# cat.net
KiCad netlist of a schematic drawn in EAGLE
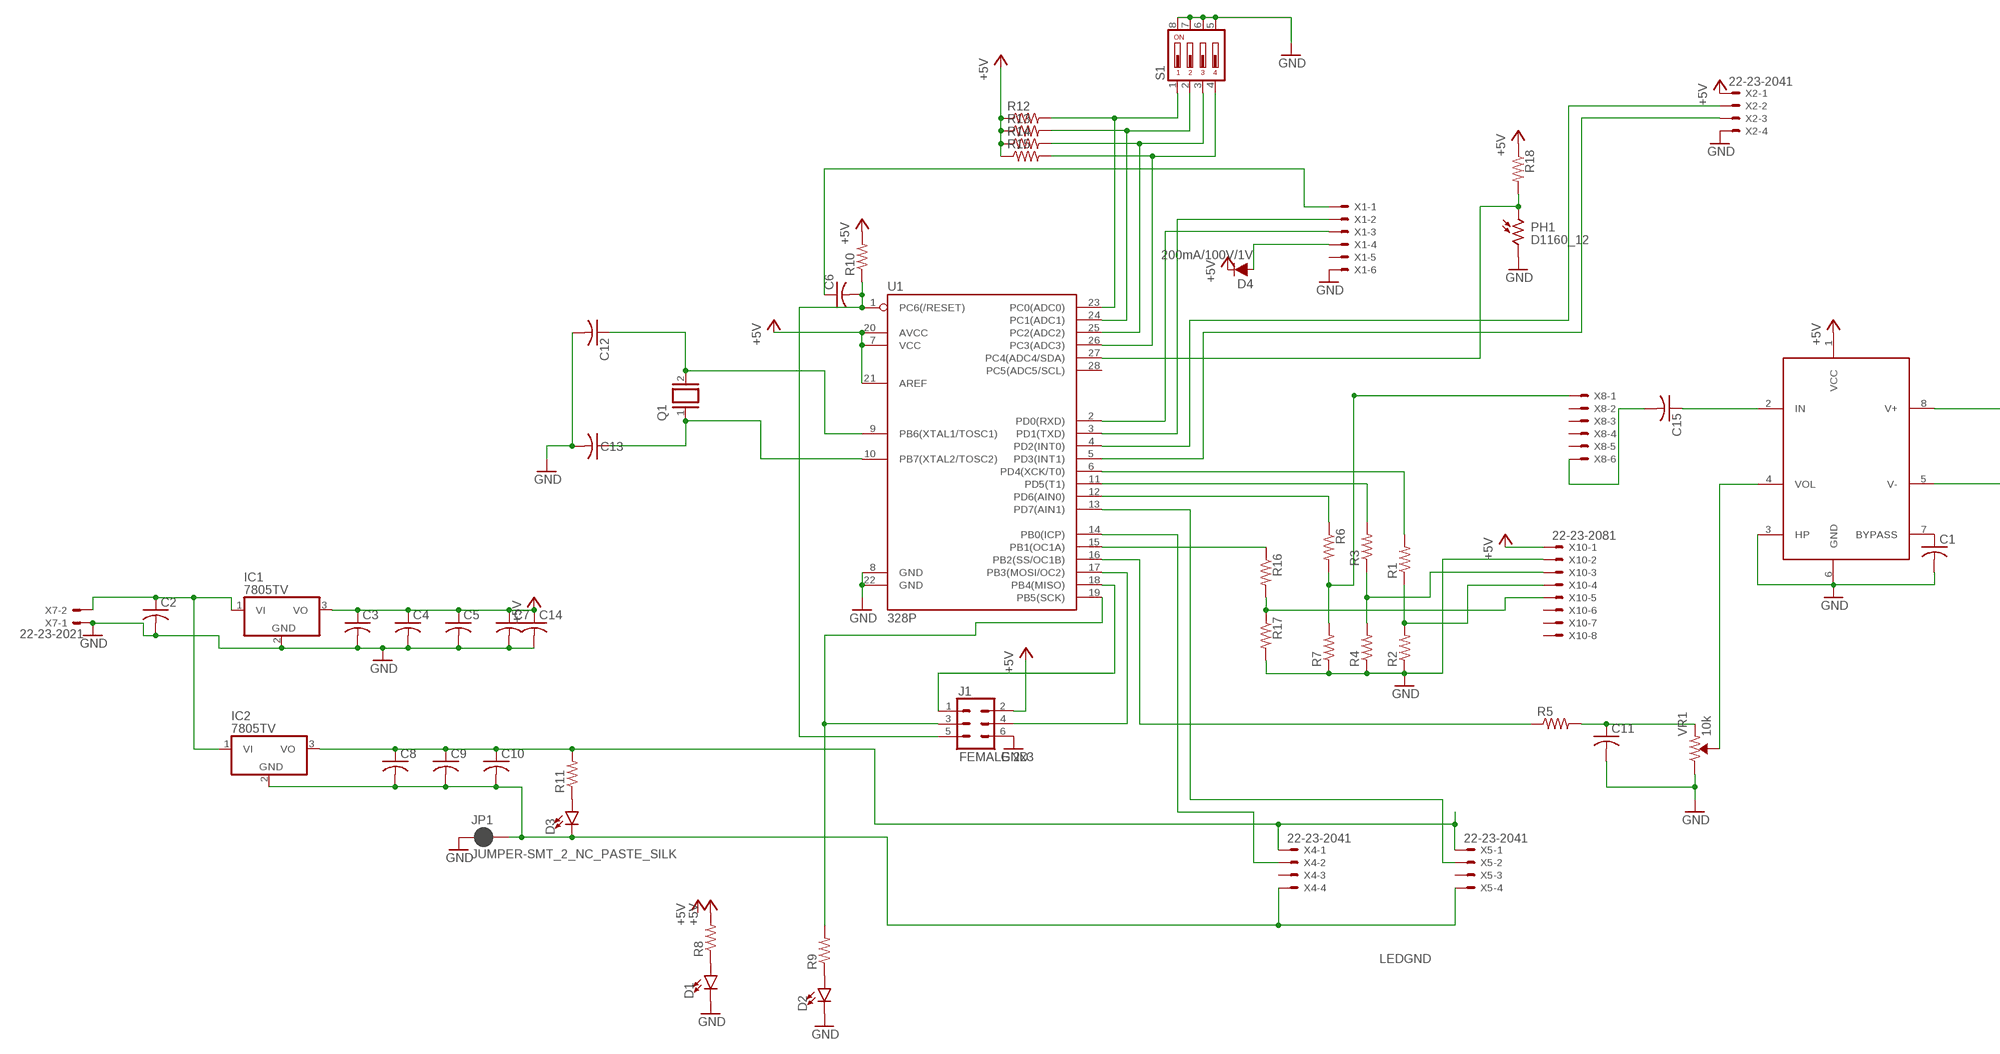
[diagram p0: schematic, sheet 1, part 1 of 2]
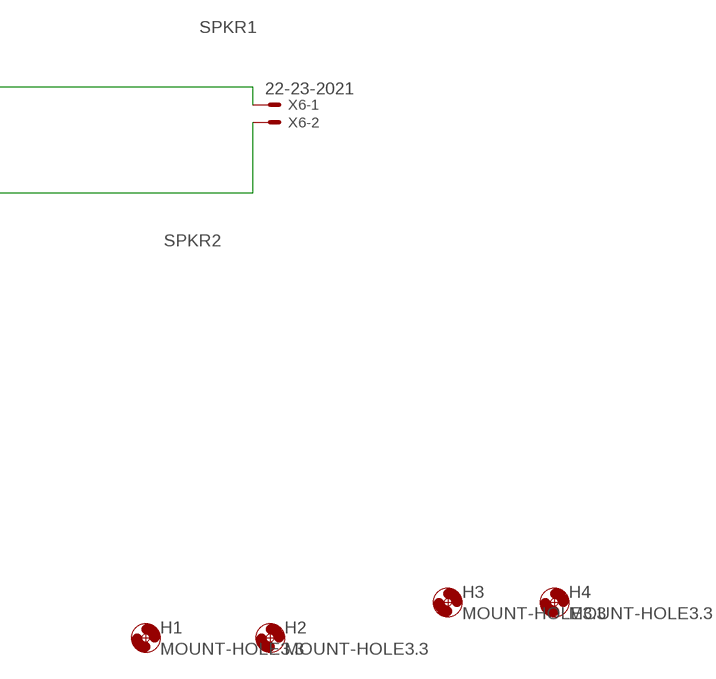
[diagram p1: schematic, sheet 1, part 2 of 2]

(export (version "E")
  (design (tool "Eeschema 10.0.6"))
  (components
    (comp (ref "C1")
      (value "C-US025-024X044")
      (footprint "eagle-import:C025-024X044")
      (libsource (lib "eagle-import") (part "C-US025-024X044"))
    )
    (comp (ref "C2")
      (value "C-US025-024X044")
      (footprint "eagle-import:C025-024X044")
      (libsource (lib "eagle-import") (part "C-US025-024X044"))
    )
    (comp (ref "C3")
      (value "C-US025-024X044")
      (footprint "eagle-import:C025-024X044")
      (libsource (lib "eagle-import") (part "C-US025-024X044"))
    )
    (comp (ref "C4")
      (value "C-US025-024X044")
      (footprint "eagle-import:C025-024X044")
      (libsource (lib "eagle-import") (part "C-US025-024X044"))
    )
    (comp (ref "C5")
      (value "C-US025-024X044")
      (footprint "eagle-import:C025-024X044")
      (libsource (lib "eagle-import") (part "C-US025-024X044"))
    )
    (comp (ref "C6")
      (value "C-US025-024X044")
      (footprint "eagle-import:C025-024X044")
      (libsource (lib "eagle-import") (part "C-US025-024X044"))
    )
    (comp (ref "C7")
      (value "C-US025-024X044")
      (footprint "eagle-import:C025-024X044")
      (libsource (lib "eagle-import") (part "C-US025-024X044"))
    )
    (comp (ref "C8")
      (value "C-US025-024X044")
      (footprint "eagle-import:C025-024X044")
      (libsource (lib "eagle-import") (part "C-US025-024X044"))
    )
    (comp (ref "C9")
      (value "C-US025-024X044")
      (footprint "eagle-import:C025-024X044")
      (libsource (lib "eagle-import") (part "C-US025-024X044"))
    )
    (comp (ref "C10")
      (value "C-US025-024X044")
      (footprint "eagle-import:C025-024X044")
      (libsource (lib "eagle-import") (part "C-US025-024X044"))
    )
    (comp (ref "C11")
      (value "C-US025-024X044")
      (footprint "eagle-import:C025-024X044")
      (libsource (lib "eagle-import") (part "C-US025-024X044"))
    )
    (comp (ref "C12")
      (value "C-US025-024X044")
      (footprint "eagle-import:C025-024X044")
      (libsource (lib "eagle-import") (part "C-US025-024X044"))
    )
    (comp (ref "C13")
      (value "C-US025-024X044")
      (footprint "eagle-import:C025-024X044")
      (libsource (lib "eagle-import") (part "C-US025-024X044"))
    )
    (comp (ref "C14")
      (value "C-US025-024X044")
      (footprint "eagle-import:C025-024X044")
      (libsource (lib "eagle-import") (part "C-US025-024X044"))
    )
    (comp (ref "C15")
      (value "C-US025-024X044")
      (footprint "eagle-import:C025-024X044")
      (libsource (lib "eagle-import") (part "C-US025-024X044"))
    )
    (comp (ref "D1")
      (value "LED-3MM-NO_SILK")
      (footprint "eagle-import:LED_3MM-NS")
      (libsource (lib "eagle-import") (part "LED-3MM-NO_SILK"))
    )
    (comp (ref "D2")
      (value "LED-3MM-NO_SILK")
      (footprint "eagle-import:LED_3MM-NS")
      (libsource (lib "eagle-import") (part "LED-3MM-NO_SILK"))
    )
    (comp (ref "D3")
      (value "LED-3MM-NO_SILK")
      (footprint "eagle-import:LED_3MM-NS")
      (libsource (lib "eagle-import") (part "LED-3MM-NO_SILK"))
    )
    (comp (ref "D4")
      (value "200mA/100V/1V")
      (footprint "eagle-import:DIODE-1N4148")
      (libsource (lib "eagle-import") (part "DIODE-1N4148"))
    )
    (comp (ref "H1")
      (value "MOUNT-HOLE3.3")
      (footprint "eagle-import:3,3")
      (libsource (lib "eagle-import") (part "MOUNT-HOLE3.3"))
    )
    (comp (ref "H2")
      (value "MOUNT-HOLE3.3")
      (footprint "eagle-import:3,3")
      (libsource (lib "eagle-import") (part "MOUNT-HOLE3.3"))
    )
    (comp (ref "H3")
      (value "MOUNT-HOLE3.3")
      (footprint "eagle-import:3,3")
      (libsource (lib "eagle-import") (part "MOUNT-HOLE3.3"))
    )
    (comp (ref "H4")
      (value "MOUNT-HOLE3.3")
      (footprint "eagle-import:3,3")
      (libsource (lib "eagle-import") (part "MOUNT-HOLE3.3"))
    )
    (comp (ref "IC1")
      (value "7805TV")
      (footprint "eagle-import:TO220V")
      (libsource (lib "eagle-import") (part "78TV05"))
    )
    (comp (ref "IC2")
      (value "7805TV")
      (footprint "eagle-import:TO220V")
      (libsource (lib "eagle-import") (part "78TV05"))
    )
    (comp (ref "J1")
      (value "FEMALE 2x3")
      (footprint "eagle-import:2X3")
      (libsource (lib "eagle-import") (part "CONN_03X2FEMALE"))
    )
    (comp (ref "JP1")
      (value "JUMPER-SMT_2_NC_PASTE_SILK")
      (footprint "eagle-import:SMT-JUMPER_2_NC_PASTE_SILK")
      (libsource (lib "eagle-import") (part "JUMPER-SMT_2_NC_PASTE_SILK"))
    )
    (comp (ref "PH1")
      (value "D1160_12")
      (footprint "eagle-import:D11XX")
      (libsource (lib "eagle-import") (part "D1160_12"))
    )
    (comp (ref "Q1")
      (value "XTAL/S")
      (footprint "eagle-import:QS")
      (libsource (lib "eagle-import") (part "XTAL/S"))
    )
    (comp (ref "R1")
      (value "R-US_R0805")
      (footprint "eagle-import:R0805")
      (libsource (lib "eagle-import") (part "R-US_R0805"))
    )
    (comp (ref "R2")
      (value "R-US_R0805")
      (footprint "eagle-import:R0805")
      (libsource (lib "eagle-import") (part "R-US_R0805"))
    )
    (comp (ref "R3")
      (value "R-US_R0805")
      (footprint "eagle-import:R0805")
      (libsource (lib "eagle-import") (part "R-US_R0805"))
    )
    (comp (ref "R4")
      (value "R-US_R0805")
      (footprint "eagle-import:R0805")
      (libsource (lib "eagle-import") (part "R-US_R0805"))
    )
    (comp (ref "R5")
      (value "R-US_R0805")
      (footprint "eagle-import:R0805")
      (libsource (lib "eagle-import") (part "R-US_R0805"))
    )
    (comp (ref "R6")
      (value "R-US_R0805")
      (footprint "eagle-import:R0805")
      (libsource (lib "eagle-import") (part "R-US_R0805"))
    )
    (comp (ref "R7")
      (value "R-US_R0805")
      (footprint "eagle-import:R0805")
      (libsource (lib "eagle-import") (part "R-US_R0805"))
    )
    (comp (ref "R8")
      (value "R-US_R0805")
      (footprint "eagle-import:R0805")
      (libsource (lib "eagle-import") (part "R-US_R0805"))
    )
    (comp (ref "R9")
      (value "R-US_R0805")
      (footprint "eagle-import:R0805")
      (libsource (lib "eagle-import") (part "R-US_R0805"))
    )
    (comp (ref "R10")
      (value "R-US_R0805")
      (footprint "eagle-import:R0805")
      (libsource (lib "eagle-import") (part "R-US_R0805"))
    )
    (comp (ref "R11")
      (value "R-US_R0805")
      (footprint "eagle-import:R0805")
      (libsource (lib "eagle-import") (part "R-US_R0805"))
    )
    (comp (ref "R12")
      (value "R-US_R0805")
      (footprint "eagle-import:R0805")
      (libsource (lib "eagle-import") (part "R-US_R0805"))
    )
    (comp (ref "R13")
      (value "R-US_R0805")
      (footprint "eagle-import:R0805")
      (libsource (lib "eagle-import") (part "R-US_R0805"))
    )
    (comp (ref "R14")
      (value "R-US_R0805")
      (footprint "eagle-import:R0805")
      (libsource (lib "eagle-import") (part "R-US_R0805"))
    )
    (comp (ref "R15")
      (value "R-US_R0805")
      (footprint "eagle-import:R0805")
      (libsource (lib "eagle-import") (part "R-US_R0805"))
    )
    (comp (ref "R16")
      (value "R-US_R0805")
      (footprint "eagle-import:R0805")
      (libsource (lib "eagle-import") (part "R-US_R0805"))
    )
    (comp (ref "R17")
      (value "R-US_R0805")
      (footprint "eagle-import:R0805")
      (libsource (lib "eagle-import") (part "R-US_R0805"))
    )
    (comp (ref "R18")
      (value "R-US_R0805")
      (footprint "eagle-import:R0805")
      (libsource (lib "eagle-import") (part "R-US_R0805"))
    )
    (comp (ref "S1")
      (value "DIP04YL")
      (footprint "eagle-import:DIP04YL")
      (libsource (lib "eagle-import") (part "DIP04YL"))
    )
    (comp (ref "U$1")
      (value "LM4875")
      (footprint "eagle-import:SO8")
      (libsource (lib "eagle-import") (part "LM4875"))
    )
    (comp (ref "U1")
      (value "328P")
      (footprint "eagle-import:DIP28")
      (libsource (lib "eagle-import") (part "ATMEGA328P_PDIP"))
    )
    (comp (ref "VR1")
      (value "10k")
      (footprint "eagle-import:TRIMPOT-PTH-3386U")
      (libsource (lib "eagle-import") (part "TRIMPOT-PTH-10MM-KNOB-1/2W-10%"))
    )
    (comp (ref "X1")
      (value "22-23-2061")
      (footprint "eagle-import:22-23-2061")
      (fields (field (name "MF") "MOLEX"))
      (libsource (lib "eagle-import") (part "22-23-2061"))
    )
    (comp (ref "X2")
      (value "22-23-2041")
      (footprint "eagle-import:22-23-2041")
      (fields (field (name "MF") "MOLEX"))
      (libsource (lib "eagle-import") (part "22-23-2041"))
    )
    (comp (ref "X4")
      (value "22-23-2041")
      (footprint "eagle-import:22-23-2041")
      (fields (field (name "MF") "MOLEX"))
      (libsource (lib "eagle-import") (part "22-23-2041"))
    )
    (comp (ref "X5")
      (value "22-23-2041")
      (footprint "eagle-import:22-23-2041")
      (fields (field (name "MF") "MOLEX"))
      (libsource (lib "eagle-import") (part "22-23-2041"))
    )
    (comp (ref "X6")
      (value "22-23-2021")
      (footprint "eagle-import:22-23-2021")
      (fields (field (name "MF") "MOLEX"))
      (libsource (lib "eagle-import") (part "22-23-2021"))
    )
    (comp (ref "X7")
      (value "22-23-2021")
      (footprint "eagle-import:22-23-2021")
      (fields (field (name "MF") "MOLEX"))
      (libsource (lib "eagle-import") (part "22-23-2021"))
    )
    (comp (ref "X8")
      (value "22-23-2061")
      (footprint "eagle-import:22-23-2061")
      (fields (field (name "MF") "MOLEX"))
      (libsource (lib "eagle-import") (part "22-23-2061"))
    )
    (comp (ref "X10")
      (value "22-23-2081")
      (footprint "eagle-import:22-23-2081")
      (fields (field (name "MF") "MOLEX"))
      (libsource (lib "eagle-import") (part "22-23-2081"))
    )
  )
  (nets
    (net (code "1") (name "+5V") (class "Default")
      (node (ref "C14") (pin "1") (pinfunction "1_1") (pintype "passive"))
      (node (ref "C3") (pin "1") (pinfunction "1_1") (pintype "passive"))
      (node (ref "C4") (pin "1") (pinfunction "1_1") (pintype "passive"))
      (node (ref "C5") (pin "1") (pinfunction "1_1") (pintype "passive"))
      (node (ref "C7") (pin "1") (pinfunction "1_1") (pintype "passive"))
      (node (ref "D4") (pin "C") (pinfunction "C_C") (pintype "passive"))
      (node (ref "IC1") (pin "3") (pinfunction "VO_3") (pintype "passive"))
      (node (ref "J1") (pin "2") (pinfunction "2_2") (pintype "bidirectional"))
      (node (ref "R10") (pin "2") (pinfunction "2_2") (pintype "passive"))
      (node (ref "R12") (pin "1") (pinfunction "1_1") (pintype "passive"))
      (node (ref "R13") (pin "1") (pinfunction "1_1") (pintype "passive"))
      (node (ref "R14") (pin "1") (pinfunction "1_1") (pintype "passive"))
      (node (ref "R15") (pin "1") (pinfunction "1_1") (pintype "passive"))
      (node (ref "R18") (pin "1") (pinfunction "1_1") (pintype "passive"))
      (node (ref "R8") (pin "2") (pinfunction "2_2") (pintype "passive"))
      (node (ref "U$1") (pin "1") (pinfunction "VCC_1") (pintype "bidirectional"))
      (node (ref "U1") (pin "20") (pinfunction "AVCC_20") (pintype "bidirectional"))
      (node (ref "U1") (pin "21") (pinfunction "AREF_21") (pintype "bidirectional"))
      (node (ref "U1") (pin "7") (pinfunction "VCC_7") (pintype "bidirectional"))
      (node (ref "X10") (pin "1") (pinfunction "S_1") (pintype "passive"))
      (node (ref "X2") (pin "1") (pinfunction "S_1") (pintype "passive"))
    )
    (net (code "2") (name "/LEDGND") (class "Default")
      (node (ref "C10") (pin "2") (pinfunction "2_2") (pintype "passive"))
      (node (ref "C8") (pin "2") (pinfunction "2_2") (pintype "passive"))
      (node (ref "C9") (pin "2") (pinfunction "2_2") (pintype "passive"))
      (node (ref "D3") (pin "K") (pinfunction "C_K") (pintype "passive"))
      (node (ref "IC2") (pin "2") (pinfunction "GND_2") (pintype "passive"))
      (node (ref "JP1") (pin "2") (pinfunction "2_2") (pintype "passive"))
      (node (ref "X4") (pin "4") (pinfunction "S_4") (pintype "passive"))
      (node (ref "X5") (pin "4") (pinfunction "S_4") (pintype "passive"))
    )
    (net (code "3") (name "/SPKR1") (class "Default")
      (node (ref "U$1") (pin "8") (pinfunction "V+_8") (pintype "bidirectional"))
      (node (ref "X6") (pin "1") (pinfunction "S_1") (pintype "passive"))
    )
    (net (code "4") (name "/SPKR2") (class "Default")
      (node (ref "U$1") (pin "5") (pinfunction "V-_5") (pintype "bidirectional"))
      (node (ref "X6") (pin "2") (pinfunction "S_2") (pintype "passive"))
    )
    (net (code "5") (name "GND") (class "Default")
      (node (ref "C1") (pin "2") (pinfunction "2_2") (pintype "passive"))
      (node (ref "C11") (pin "2") (pinfunction "2_2") (pintype "passive"))
      (node (ref "C12") (pin "2") (pinfunction "2_2") (pintype "passive"))
      (node (ref "C13") (pin "2") (pinfunction "2_2") (pintype "passive"))
      (node (ref "C14") (pin "2") (pinfunction "2_2") (pintype "passive"))
      (node (ref "C2") (pin "2") (pinfunction "2_2") (pintype "passive"))
      (node (ref "C3") (pin "2") (pinfunction "2_2") (pintype "passive"))
      (node (ref "C4") (pin "2") (pinfunction "2_2") (pintype "passive"))
      (node (ref "C5") (pin "2") (pinfunction "2_2") (pintype "passive"))
      (node (ref "C7") (pin "2") (pinfunction "2_2") (pintype "passive"))
      (node (ref "D1") (pin "K") (pinfunction "C_K") (pintype "passive"))
      (node (ref "D2") (pin "K") (pinfunction "C_K") (pintype "passive"))
      (node (ref "IC1") (pin "2") (pinfunction "GND_2") (pintype "passive"))
      (node (ref "J1") (pin "6") (pinfunction "6_6") (pintype "bidirectional"))
      (node (ref "JP1") (pin "1") (pinfunction "1_1") (pintype "passive"))
      (node (ref "PH1") (pin "2") (pinfunction "2_2") (pintype "passive"))
      (node (ref "R17") (pin "2") (pinfunction "2_2") (pintype "passive"))
      (node (ref "R2") (pin "1") (pinfunction "1_1") (pintype "passive"))
      (node (ref "R4") (pin "1") (pinfunction "1_1") (pintype "passive"))
      (node (ref "R7") (pin "1") (pinfunction "1_1") (pintype "passive"))
      (node (ref "S1") (pin "5") (pinfunction "5_5") (pintype "passive"))
      (node (ref "S1") (pin "6") (pinfunction "6_6") (pintype "passive"))
      (node (ref "S1") (pin "7") (pinfunction "7_7") (pintype "passive"))
      (node (ref "S1") (pin "8") (pinfunction "8_8") (pintype "passive"))
      (node (ref "U$1") (pin "3") (pinfunction "HP_3") (pintype "bidirectional"))
      (node (ref "U$1") (pin "6") (pinfunction "GND_6") (pintype "bidirectional"))
      (node (ref "U1") (pin "22") (pinfunction "GND_22") (pintype "bidirectional"))
      (node (ref "U1") (pin "8") (pinfunction "GND_8") (pintype "bidirectional"))
      (node (ref "VR1") (pin "3") (pinfunction "CW_3") (pintype "passive"))
      (node (ref "X1") (pin "6") (pinfunction "S_6") (pintype "passive"))
      (node (ref "X10") (pin "2") (pinfunction "S_2") (pintype "passive"))
      (node (ref "X2") (pin "4") (pinfunction "S_4") (pintype "passive"))
      (node (ref "X7") (pin "1") (pinfunction "S_1") (pintype "passive"))
    )
    (net (code "6") (name "Net-(D1-PadA)") (class "Default")
      (node (ref "D1") (pin "A") (pinfunction "A_A") (pintype "passive"))
      (node (ref "R8") (pin "1") (pinfunction "1_1") (pintype "passive"))
    )
    (net (code "7") (name "Net-(D2-PadA)") (class "Default")
      (node (ref "D2") (pin "A") (pinfunction "A_A") (pintype "passive"))
      (node (ref "R9") (pin "1") (pinfunction "1_1") (pintype "passive"))
    )
    (net (code "8") (name "Net-(D3-PadA)") (class "Default")
      (node (ref "D3") (pin "A") (pinfunction "A_A") (pintype "passive"))
      (node (ref "R11") (pin "1") (pinfunction "1_1") (pintype "passive"))
    )
    (net (code "9") (name "Net-(IC1-VI)") (class "Default")
      (node (ref "C2") (pin "1") (pinfunction "1_1") (pintype "passive"))
      (node (ref "IC1") (pin "1") (pinfunction "VI_1") (pintype "input"))
      (node (ref "IC2") (pin "1") (pinfunction "VI_1") (pintype "input"))
      (node (ref "X7") (pin "2") (pinfunction "S_2") (pintype "passive"))
    )
    (net (code "10") (name "Net-(IC2-VO)") (class "Default")
      (node (ref "C10") (pin "1") (pinfunction "1_1") (pintype "passive"))
      (node (ref "C8") (pin "1") (pinfunction "1_1") (pintype "passive"))
      (node (ref "C9") (pin "1") (pinfunction "1_1") (pintype "passive"))
      (node (ref "IC2") (pin "3") (pinfunction "VO_3") (pintype "passive"))
      (node (ref "R11") (pin "2") (pinfunction "2_2") (pintype "passive"))
      (node (ref "X4") (pin "1") (pinfunction "S_1") (pintype "passive"))
      (node (ref "X5") (pin "1") (pinfunction "S_1") (pintype "passive"))
    )
    (net (code "11") (name "Net-(U$1-BYPASS)") (class "Default")
      (node (ref "C1") (pin "1") (pinfunction "1_1") (pintype "passive"))
      (node (ref "U$1") (pin "7") (pinfunction "BYPASS_7") (pintype "bidirectional"))
    )
    (net (code "12") (name "Net-(U$1-IN)") (class "Default")
      (node (ref "C15") (pin "1") (pinfunction "1_1") (pintype "passive"))
      (node (ref "U$1") (pin "2") (pinfunction "IN_2") (pintype "bidirectional"))
    )
    (net (code "13") (name "Net-(U$1-VOL)") (class "Default")
      (node (ref "U$1") (pin "4") (pinfunction "VOL_4") (pintype "bidirectional"))
      (node (ref "VR1") (pin "2") (pinfunction "WIPER_2") (pintype "passive"))
    )
    (net (code "14") (name "Net-(U1-PB0(ICP))") (class "Default")
      (node (ref "U1") (pin "14") (pinfunction "PB0(ICP)_14") (pintype "bidirectional"))
      (node (ref "X4") (pin "2") (pinfunction "S_2") (pintype "passive"))
    )
    (net (code "15") (name "Net-(U1-PB1(OC1A))") (class "Default")
      (node (ref "R16") (pin "1") (pinfunction "1_1") (pintype "passive"))
      (node (ref "U1") (pin "15") (pinfunction "PB1(OC1A)_15") (pintype "bidirectional"))
    )
    (net (code "16") (name "Net-(U1-PB2(SS{slash}OC1B))") (class "Default")
      (node (ref "R5") (pin "1") (pinfunction "1_1") (pintype "passive"))
      (node (ref "U1") (pin "16") (pinfunction "PB2(SS/OC1B)_16") (pintype "bidirectional"))
    )
    (net (code "17") (name "Net-(U1-PB3(MOSI{slash}OC2))") (class "Default")
      (node (ref "J1") (pin "4") (pinfunction "4_4") (pintype "bidirectional"))
      (node (ref "U1") (pin "17") (pinfunction "PB3(MOSI/OC2)_17") (pintype "bidirectional"))
    )
    (net (code "18") (name "Net-(U1-PB4(MISO))") (class "Default")
      (node (ref "J1") (pin "1") (pinfunction "1_1") (pintype "bidirectional"))
      (node (ref "U1") (pin "18") (pinfunction "PB4(MISO)_18") (pintype "bidirectional"))
    )
    (net (code "19") (name "Net-(U1-PB5(SCK))") (class "Default")
      (node (ref "J1") (pin "3") (pinfunction "3_3") (pintype "bidirectional"))
      (node (ref "R9") (pin "2") (pinfunction "2_2") (pintype "passive"))
      (node (ref "U1") (pin "19") (pinfunction "PB5(SCK)_19") (pintype "bidirectional"))
    )
    (net (code "20") (name "Net-(U1-PB6(XTAL1{slash}TOSC1))") (class "Default")
      (node (ref "C12") (pin "1") (pinfunction "1_1") (pintype "passive"))
      (node (ref "Q1") (pin "2") (pinfunction "2_2") (pintype "passive"))
      (node (ref "U1") (pin "9") (pinfunction "PB6(XTAL1/TOSC1)_9") (pintype "bidirectional"))
    )
    (net (code "21") (name "Net-(U1-PB7(XTAL2{slash}TOSC2))") (class "Default")
      (node (ref "C13") (pin "1") (pinfunction "1_1") (pintype "passive"))
      (node (ref "Q1") (pin "1") (pinfunction "1_1") (pintype "passive"))
      (node (ref "U1") (pin "10") (pinfunction "PB7(XTAL2/TOSC2)_10") (pintype "bidirectional"))
    )
    (net (code "22") (name "Net-(U1-PC0(ADC0))") (class "Default")
      (node (ref "R12") (pin "2") (pinfunction "2_2") (pintype "passive"))
      (node (ref "S1") (pin "1") (pinfunction "1_1") (pintype "passive"))
      (node (ref "U1") (pin "23") (pinfunction "PC0(ADC0)_23") (pintype "bidirectional"))
    )
    (net (code "23") (name "Net-(U1-PC1(ADC1))") (class "Default")
      (node (ref "R13") (pin "2") (pinfunction "2_2") (pintype "passive"))
      (node (ref "S1") (pin "2") (pinfunction "2_2") (pintype "passive"))
      (node (ref "U1") (pin "24") (pinfunction "PC1(ADC1)_24") (pintype "bidirectional"))
    )
    (net (code "24") (name "Net-(U1-PC2(ADC2))") (class "Default")
      (node (ref "R14") (pin "2") (pinfunction "2_2") (pintype "passive"))
      (node (ref "S1") (pin "3") (pinfunction "3_3") (pintype "passive"))
      (node (ref "U1") (pin "25") (pinfunction "PC2(ADC2)_25") (pintype "bidirectional"))
    )
    (net (code "25") (name "Net-(U1-PC3(ADC3))") (class "Default")
      (node (ref "R15") (pin "2") (pinfunction "2_2") (pintype "passive"))
      (node (ref "S1") (pin "4") (pinfunction "4_4") (pintype "passive"))
      (node (ref "U1") (pin "26") (pinfunction "PC3(ADC3)_26") (pintype "bidirectional"))
    )
    (net (code "26") (name "Net-(U1-PC4(ADC4{slash}SDA))") (class "Default")
      (node (ref "PH1") (pin "1") (pinfunction "1_1") (pintype "passive"))
      (node (ref "R18") (pin "2") (pinfunction "2_2") (pintype "passive"))
      (node (ref "U1") (pin "27") (pinfunction "PC4(ADC4/SDA)_27") (pintype "bidirectional"))
    )
    (net (code "27") (name "Net-(U1-PC6({slash}RESET))") (class "Default")
      (node (ref "C6") (pin "2") (pinfunction "2_2") (pintype "passive"))
      (node (ref "J1") (pin "5") (pinfunction "5_5") (pintype "bidirectional"))
      (node (ref "R10") (pin "1") (pinfunction "1_1") (pintype "passive"))
      (node (ref "U1") (pin "1") (pinfunction "PC6(/RESET)_1") (pintype "bidirectional"))
    )
    (net (code "28") (name "Net-(U1-PD0(RXD))") (class "Default")
      (node (ref "U1") (pin "2") (pinfunction "PD0(RXD)_2") (pintype "bidirectional"))
      (node (ref "X1") (pin "3") (pinfunction "S_3") (pintype "passive"))
    )
    (net (code "29") (name "Net-(U1-PD1(TXD))") (class "Default")
      (node (ref "U1") (pin "3") (pinfunction "PD1(TXD)_3") (pintype "bidirectional"))
      (node (ref "X1") (pin "2") (pinfunction "S_2") (pintype "passive"))
    )
    (net (code "30") (name "Net-(U1-PD2(INT0))") (class "Default")
      (node (ref "U1") (pin "4") (pinfunction "PD2(INT0)_4") (pintype "bidirectional"))
      (node (ref "X2") (pin "2") (pinfunction "S_2") (pintype "passive"))
    )
    (net (code "31") (name "Net-(U1-PD3(INT1))") (class "Default")
      (node (ref "U1") (pin "5") (pinfunction "PD3(INT1)_5") (pintype "bidirectional"))
      (node (ref "X2") (pin "3") (pinfunction "S_3") (pintype "passive"))
    )
    (net (code "32") (name "Net-(U1-PD4(XCK{slash}T0))") (class "Default")
      (node (ref "R1") (pin "2") (pinfunction "2_2") (pintype "passive"))
      (node (ref "U1") (pin "6") (pinfunction "PD4(XCK/T0)_6") (pintype "bidirectional"))
    )
    (net (code "33") (name "Net-(U1-PD5(T1))") (class "Default")
      (node (ref "R3") (pin "2") (pinfunction "2_2") (pintype "passive"))
      (node (ref "U1") (pin "11") (pinfunction "PD5(T1)_11") (pintype "bidirectional"))
    )
    (net (code "34") (name "Net-(U1-PD6(AIN0))") (class "Default")
      (node (ref "R6") (pin "1") (pinfunction "1_1") (pintype "passive"))
      (node (ref "U1") (pin "12") (pinfunction "PD6(AIN0)_12") (pintype "bidirectional"))
    )
    (net (code "35") (name "Net-(U1-PD7(AIN1))") (class "Default")
      (node (ref "U1") (pin "13") (pinfunction "PD7(AIN1)_13") (pintype "bidirectional"))
      (node (ref "X5") (pin "2") (pinfunction "S_2") (pintype "passive"))
    )
    (net (code "36") (name "Net-(VR1-CCW)") (class "Default")
      (node (ref "C11") (pin "1") (pinfunction "1_1") (pintype "passive"))
      (node (ref "R5") (pin "2") (pinfunction "2_2") (pintype "passive"))
      (node (ref "VR1") (pin "1") (pinfunction "CCW_1") (pintype "passive"))
    )
    (net (code "37") (name "Net-(X1A-S)") (class "Default")
      (node (ref "C6") (pin "1") (pinfunction "1_1") (pintype "passive"))
      (node (ref "X1") (pin "1") (pinfunction "S_1") (pintype "passive"))
    )
    (net (code "38") (name "Net-(X1D-S)") (class "Default")
      (node (ref "D4") (pin "A") (pinfunction "A_A") (pintype "passive"))
      (node (ref "X1") (pin "4") (pinfunction "S_4") (pintype "passive"))
    )
    (net (code "39") (name "Net-(X8A-S)") (class "Default")
      (node (ref "R6") (pin "2") (pinfunction "2_2") (pintype "passive"))
      (node (ref "R7") (pin "2") (pinfunction "2_2") (pintype "passive"))
      (node (ref "X8") (pin "1") (pinfunction "S_1") (pintype "passive"))
    )
    (net (code "40") (name "Net-(X8F-S)") (class "Default")
      (node (ref "C15") (pin "2") (pinfunction "2_2") (pintype "passive"))
      (node (ref "X8") (pin "6") (pinfunction "S_6") (pintype "passive"))
    )
    (net (code "41") (name "Net-(X10C-S)") (class "Default")
      (node (ref "R3") (pin "1") (pinfunction "1_1") (pintype "passive"))
      (node (ref "R4") (pin "2") (pinfunction "2_2") (pintype "passive"))
      (node (ref "X10") (pin "3") (pinfunction "S_3") (pintype "passive"))
    )
    (net (code "42") (name "Net-(X10D-S)") (class "Default")
      (node (ref "R1") (pin "1") (pinfunction "1_1") (pintype "passive"))
      (node (ref "R2") (pin "2") (pinfunction "2_2") (pintype "passive"))
      (node (ref "X10") (pin "4") (pinfunction "S_4") (pintype "passive"))
    )
    (net (code "43") (name "Net-(X10E-S)") (class "Default")
      (node (ref "R16") (pin "2") (pinfunction "2_2") (pintype "passive"))
      (node (ref "R17") (pin "1") (pinfunction "1_1") (pintype "passive"))
      (node (ref "X10") (pin "5") (pinfunction "S_5") (pintype "passive"))
    )
    (net (code "44") (name "unconnected-(U1-PC5(ADC5{slash}SCL)-Pad28)") (class "Default")
      (node (ref "U1") (pin "28") (pinfunction "PC5(ADC5/SCL)_28") (pintype "bidirectional"))
    )
    (net (code "45") (name "unconnected-(X1E-S-Pad5)") (class "Default")
      (node (ref "X1") (pin "5") (pinfunction "S_5") (pintype "passive"))
    )
    (net (code "46") (name "unconnected-(X4C-S-Pad3)") (class "Default")
      (node (ref "X4") (pin "3") (pinfunction "S_3") (pintype "passive"))
    )
    (net (code "47") (name "unconnected-(X5C-S-Pad3)") (class "Default")
      (node (ref "X5") (pin "3") (pinfunction "S_3") (pintype "passive"))
    )
    (net (code "48") (name "unconnected-(X8B-S-Pad2)") (class "Default")
      (node (ref "X8") (pin "2") (pinfunction "S_2") (pintype "passive"))
    )
    (net (code "49") (name "unconnected-(X8C-S-Pad3)") (class "Default")
      (node (ref "X8") (pin "3") (pinfunction "S_3") (pintype "passive"))
    )
    (net (code "50") (name "unconnected-(X8D-S-Pad4)") (class "Default")
      (node (ref "X8") (pin "4") (pinfunction "S_4") (pintype "passive"))
    )
    (net (code "51") (name "unconnected-(X8E-S-Pad5)") (class "Default")
      (node (ref "X8") (pin "5") (pinfunction "S_5") (pintype "passive"))
    )
    (net (code "52") (name "unconnected-(X10F-S-Pad6)") (class "Default")
      (node (ref "X10") (pin "6") (pinfunction "S_6") (pintype "passive"))
    )
    (net (code "53") (name "unconnected-(X10G-S-Pad7)") (class "Default")
      (node (ref "X10") (pin "7") (pinfunction "S_7") (pintype "passive"))
    )
    (net (code "54") (name "unconnected-(X10H-S-Pad8)") (class "Default")
      (node (ref "X10") (pin "8") (pinfunction "S_8") (pintype "passive"))
    )
  )
)
